# Transmission_Schematic.net
KiCad netlist of a schematic drawn in EAGLE
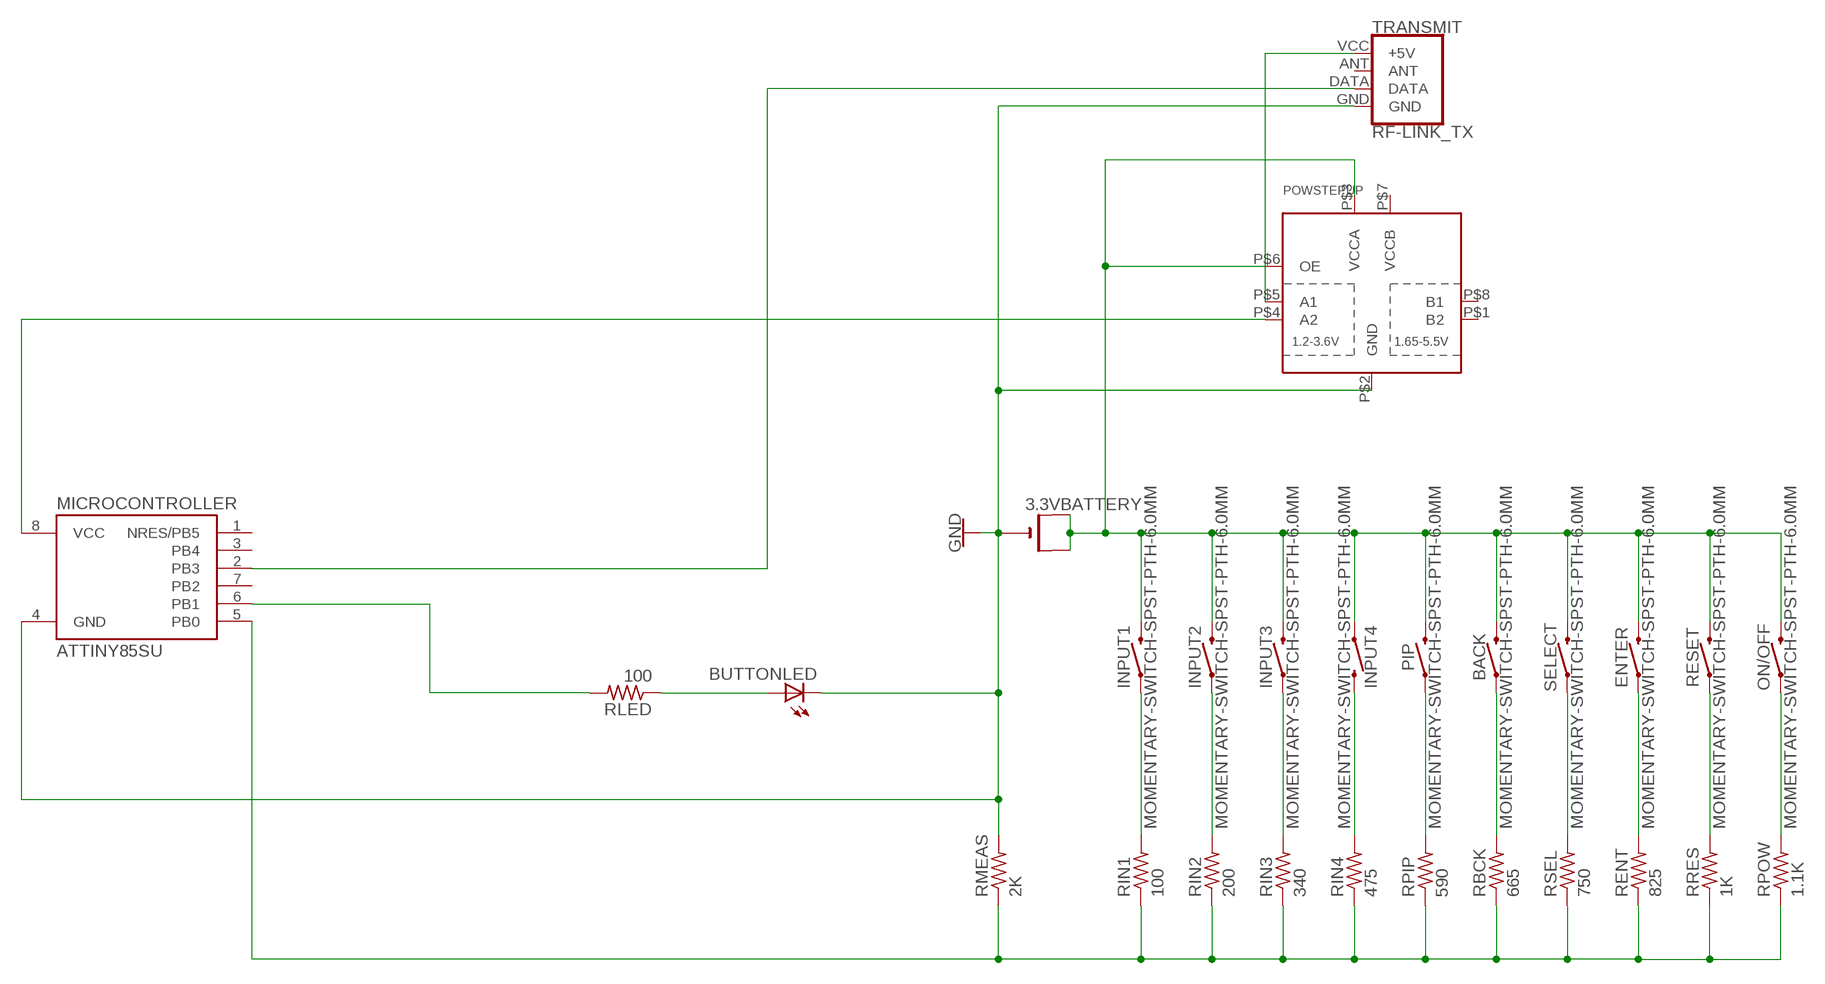
[diagram p0: schematic, sheet 1]

(export (version "E")
  (design (tool "Eeschema 10.0.6"))
  (components
    (comp (ref "3.3VBATTERY")
      (value "CR1220THM")
      (footprint "eagle-import:CR1220-THM")
      (libsource (lib "eagle-import") (part "CR1220THM"))
    )
    (comp (ref "BACK")
      (value "MOMENTARY-SWITCH-SPST-PTH-6.0MM")
      (footprint "eagle-import:TACTILE_SWITCH_PTH_6.0MM")
      (libsource (lib "eagle-import") (part "MOMENTARY-SWITCH-SPST-PTH-6.0MM"))
    )
    (comp (ref "BUTTONLED")
      (value "LEDCHIPLED_0805")
      (footprint "eagle-import:CHIPLED_0805")
      (libsource (lib "eagle-import") (part "LEDCHIPLED_0805"))
    )
    (comp (ref "ENTER")
      (value "MOMENTARY-SWITCH-SPST-PTH-6.0MM")
      (footprint "eagle-import:TACTILE_SWITCH_PTH_6.0MM")
      (libsource (lib "eagle-import") (part "MOMENTARY-SWITCH-SPST-PTH-6.0MM"))
    )
    (comp (ref "INPUT1")
      (value "MOMENTARY-SWITCH-SPST-PTH-6.0MM")
      (footprint "eagle-import:TACTILE_SWITCH_PTH_6.0MM")
      (libsource (lib "eagle-import") (part "MOMENTARY-SWITCH-SPST-PTH-6.0MM"))
    )
    (comp (ref "INPUT2")
      (value "MOMENTARY-SWITCH-SPST-PTH-6.0MM")
      (footprint "eagle-import:TACTILE_SWITCH_PTH_6.0MM")
      (libsource (lib "eagle-import") (part "MOMENTARY-SWITCH-SPST-PTH-6.0MM"))
    )
    (comp (ref "INPUT3")
      (value "MOMENTARY-SWITCH-SPST-PTH-6.0MM")
      (footprint "eagle-import:TACTILE_SWITCH_PTH_6.0MM")
      (libsource (lib "eagle-import") (part "MOMENTARY-SWITCH-SPST-PTH-6.0MM"))
    )
    (comp (ref "INPUT4")
      (value "MOMENTARY-SWITCH-SPST-PTH-6.0MM")
      (footprint "eagle-import:TACTILE_SWITCH_PTH_6.0MM")
      (libsource (lib "eagle-import") (part "MOMENTARY-SWITCH-SPST-PTH-6.0MM"))
    )
    (comp (ref "MICROCONTROLLER")
      (value "ATTINY85SU")
      (footprint "eagle-import:ATTINY85")
      (libsource (lib "eagle-import") (part "ATTINY85SU"))
    )
    (comp (ref "ON/OFF")
      (value "MOMENTARY-SWITCH-SPST-PTH-6.0MM")
      (footprint "eagle-import:TACTILE_SWITCH_PTH_6.0MM")
      (libsource (lib "eagle-import") (part "MOMENTARY-SWITCH-SPST-PTH-6.0MM"))
    )
    (comp (ref "PIP")
      (value "MOMENTARY-SWITCH-SPST-PTH-6.0MM")
      (footprint "eagle-import:TACTILE_SWITCH_PTH_6.0MM")
      (libsource (lib "eagle-import") (part "MOMENTARY-SWITCH-SPST-PTH-6.0MM"))
    )
    (comp (ref "POWSTEPUP")
      (value "TXS0102")
      (footprint "eagle-import:VFSOP-8")
      (libsource (lib "eagle-import") (part "TXS0102"))
    )
    (comp (ref "RBCK")
      (value "665")
      (footprint "eagle-import:R0805")
      (libsource (lib "eagle-import") (part "R-US_R0805"))
    )
    (comp (ref "RENT")
      (value "825")
      (footprint "eagle-import:R0805")
      (libsource (lib "eagle-import") (part "R-US_R0805"))
    )
    (comp (ref "RESET")
      (value "MOMENTARY-SWITCH-SPST-PTH-6.0MM")
      (footprint "eagle-import:TACTILE_SWITCH_PTH_6.0MM")
      (libsource (lib "eagle-import") (part "MOMENTARY-SWITCH-SPST-PTH-6.0MM"))
    )
    (comp (ref "RIN1")
      (value "100")
      (footprint "eagle-import:R0805")
      (libsource (lib "eagle-import") (part "R-US_R0805"))
    )
    (comp (ref "RIN2")
      (value "200")
      (footprint "eagle-import:R0805")
      (libsource (lib "eagle-import") (part "R-US_R0805"))
    )
    (comp (ref "RIN3")
      (value "340")
      (footprint "eagle-import:R0805")
      (libsource (lib "eagle-import") (part "R-US_R0805"))
    )
    (comp (ref "RIN4")
      (value "475")
      (footprint "eagle-import:R0805")
      (libsource (lib "eagle-import") (part "R-US_R0805"))
    )
    (comp (ref "RLED")
      (value "100")
      (footprint "eagle-import:R0805")
      (libsource (lib "eagle-import") (part "R-US_R0805"))
    )
    (comp (ref "RMEAS")
      (value "2K")
      (footprint "eagle-import:R0805")
      (libsource (lib "eagle-import") (part "R-US_R0805"))
    )
    (comp (ref "RPIP")
      (value "590")
      (footprint "eagle-import:R0805")
      (libsource (lib "eagle-import") (part "R-US_R0805"))
    )
    (comp (ref "RPOW")
      (value "1.1K")
      (footprint "eagle-import:R0805")
      (libsource (lib "eagle-import") (part "R-US_R0805"))
    )
    (comp (ref "RRES")
      (value "1K")
      (footprint "eagle-import:R0805")
      (libsource (lib "eagle-import") (part "R-US_R0805"))
    )
    (comp (ref "RSEL")
      (value "750")
      (footprint "eagle-import:R0805")
      (libsource (lib "eagle-import") (part "R-US_R0805"))
    )
    (comp (ref "SELECT")
      (value "MOMENTARY-SWITCH-SPST-PTH-6.0MM")
      (footprint "eagle-import:TACTILE_SWITCH_PTH_6.0MM")
      (libsource (lib "eagle-import") (part "MOMENTARY-SWITCH-SPST-PTH-6.0MM"))
    )
    (comp (ref "TRANSMIT")
      (value "RF-LINK_TX")
      (footprint "eagle-import:RF-LINK_TX")
      (libsource (lib "eagle-import") (part "RF-LINK_TX"))
    )
  )
  (nets
    (net (code "1") (name "GND") (class "Default")
      (node (ref "3.3VBATTERY") (pin "-") (pinfunction "-_-") (pintype "passive"))
      (node (ref "BUTTONLED") (pin "C") (pinfunction "C_C") (pintype "passive"))
      (node (ref "MICROCONTROLLER") (pin "4") (pinfunction "GND_4") (pintype "power_in"))
      (node (ref "POWSTEPUP") (pin "P$2") (pinfunction "GND_P$2") (pintype "bidirectional"))
      (node (ref "RMEAS") (pin "2") (pinfunction "2_2") (pintype "passive"))
      (node (ref "TRANSMIT") (pin "GND") (pinfunction "GND_GND") (pintype "power_in"))
    )
    (net (code "2") (name "Net-(3.3VBATTERY-+)") (class "Default")
      (node (ref "3.3VBATTERY") (pin "+1") (pinfunction "+_+1") (pintype "passive"))
      (node (ref "3.3VBATTERY") (pin "+2") (pinfunction "+1_+2") (pintype "passive"))
      (node (ref "BACK") (pin "3") (pinfunction "2_3") (pintype "passive"))
      (node (ref "ENTER") (pin "3") (pinfunction "2_3") (pintype "passive"))
      (node (ref "INPUT1") (pin "3") (pinfunction "2_3") (pintype "passive"))
      (node (ref "INPUT2") (pin "3") (pinfunction "2_3") (pintype "passive"))
      (node (ref "INPUT3") (pin "3") (pinfunction "2_3") (pintype "passive"))
      (node (ref "INPUT4") (pin "1") (pinfunction "1_1") (pintype "passive"))
      (node (ref "ON/OFF") (pin "3") (pinfunction "2_3") (pintype "passive"))
      (node (ref "PIP") (pin "3") (pinfunction "2_3") (pintype "passive"))
      (node (ref "POWSTEPUP") (pin "P$3") (pinfunction "VCCA_P$3") (pintype "bidirectional"))
      (node (ref "POWSTEPUP") (pin "P$6") (pinfunction "OE_P$6") (pintype "bidirectional"))
      (node (ref "RESET") (pin "3") (pinfunction "2_3") (pintype "passive"))
      (node (ref "SELECT") (pin "3") (pinfunction "2_3") (pintype "passive"))
    )
    (net (code "3") (name "Net-(BACK-Pad1)") (class "Default")
      (node (ref "BACK") (pin "1") (pinfunction "1_1") (pintype "passive"))
      (node (ref "RBCK") (pin "2") (pinfunction "2_2") (pintype "passive"))
    )
    (net (code "4") (name "Net-(BUTTONLED-PadA)") (class "Default")
      (node (ref "BUTTONLED") (pin "A") (pinfunction "A_A") (pintype "passive"))
      (node (ref "RLED") (pin "1") (pinfunction "1_1") (pintype "passive"))
    )
    (net (code "5") (name "Net-(ENTER-Pad1)") (class "Default")
      (node (ref "ENTER") (pin "1") (pinfunction "1_1") (pintype "passive"))
      (node (ref "RENT") (pin "2") (pinfunction "2_2") (pintype "passive"))
    )
    (net (code "6") (name "Net-(INPUT1-Pad1)") (class "Default")
      (node (ref "INPUT1") (pin "1") (pinfunction "1_1") (pintype "passive"))
      (node (ref "RIN1") (pin "2") (pinfunction "2_2") (pintype "passive"))
    )
    (net (code "7") (name "Net-(INPUT2-Pad1)") (class "Default")
      (node (ref "INPUT2") (pin "1") (pinfunction "1_1") (pintype "passive"))
      (node (ref "RIN2") (pin "2") (pinfunction "2_2") (pintype "passive"))
    )
    (net (code "8") (name "Net-(INPUT3-Pad1)") (class "Default")
      (node (ref "INPUT3") (pin "1") (pinfunction "1_1") (pintype "passive"))
      (node (ref "RIN3") (pin "2") (pinfunction "2_2") (pintype "passive"))
    )
    (net (code "9") (name "Net-(INPUT4-2)") (class "Default")
      (node (ref "INPUT4") (pin "3") (pinfunction "2_3") (pintype "passive"))
      (node (ref "RIN4") (pin "2") (pinfunction "2_2") (pintype "passive"))
    )
    (net (code "10") (name "Net-(MICROCONTROLLER-PB0)") (class "Default")
      (node (ref "MICROCONTROLLER") (pin "5") (pinfunction "PB0_5") (pintype "bidirectional"))
      (node (ref "RBCK") (pin "1") (pinfunction "1_1") (pintype "passive"))
      (node (ref "RENT") (pin "1") (pinfunction "1_1") (pintype "passive"))
      (node (ref "RIN1") (pin "1") (pinfunction "1_1") (pintype "passive"))
      (node (ref "RIN2") (pin "1") (pinfunction "1_1") (pintype "passive"))
      (node (ref "RIN3") (pin "1") (pinfunction "1_1") (pintype "passive"))
      (node (ref "RIN4") (pin "1") (pinfunction "1_1") (pintype "passive"))
      (node (ref "RMEAS") (pin "1") (pinfunction "1_1") (pintype "passive"))
      (node (ref "RPIP") (pin "1") (pinfunction "1_1") (pintype "passive"))
      (node (ref "RPOW") (pin "1") (pinfunction "1_1") (pintype "passive"))
      (node (ref "RRES") (pin "1") (pinfunction "1_1") (pintype "passive"))
      (node (ref "RSEL") (pin "1") (pinfunction "1_1") (pintype "passive"))
    )
    (net (code "11") (name "Net-(MICROCONTROLLER-PB1)") (class "Default")
      (node (ref "MICROCONTROLLER") (pin "6") (pinfunction "PB1_6") (pintype "bidirectional"))
      (node (ref "RLED") (pin "2") (pinfunction "2_2") (pintype "passive"))
    )
    (net (code "12") (name "Net-(MICROCONTROLLER-PB3)") (class "Default")
      (node (ref "MICROCONTROLLER") (pin "2") (pinfunction "PB3_2") (pintype "bidirectional"))
      (node (ref "TRANSMIT") (pin "DATA") (pinfunction "DATA_DATA") (pintype "input"))
    )
    (net (code "13") (name "Net-(MICROCONTROLLER-VCC)") (class "Default")
      (node (ref "MICROCONTROLLER") (pin "8") (pinfunction "VCC_8") (pintype "power_in"))
      (node (ref "POWSTEPUP") (pin "P$4") (pinfunction "A2_P$4") (pintype "bidirectional"))
    )
    (net (code "14") (name "Net-(ON/OFF-Pad1)") (class "Default")
      (node (ref "ON/OFF") (pin "1") (pinfunction "1_1") (pintype "passive"))
      (node (ref "RPOW") (pin "2") (pinfunction "2_2") (pintype "passive"))
    )
    (net (code "15") (name "Net-(PIP-Pad1)") (class "Default")
      (node (ref "PIP") (pin "1") (pinfunction "1_1") (pintype "passive"))
      (node (ref "RPIP") (pin "2") (pinfunction "2_2") (pintype "passive"))
    )
    (net (code "16") (name "Net-(POWSTEPUP-A1)") (class "Default")
      (node (ref "POWSTEPUP") (pin "P$5") (pinfunction "A1_P$5") (pintype "bidirectional"))
      (node (ref "TRANSMIT") (pin "VCC") (pinfunction "+5V_VCC") (pintype "power_in"))
    )
    (net (code "17") (name "Net-(RESET-Pad1)") (class "Default")
      (node (ref "RESET") (pin "1") (pinfunction "1_1") (pintype "passive"))
      (node (ref "RRES") (pin "2") (pinfunction "2_2") (pintype "passive"))
    )
    (net (code "18") (name "Net-(RSEL-Pad2)") (class "Default")
      (node (ref "RSEL") (pin "2") (pinfunction "2_2") (pintype "passive"))
      (node (ref "SELECT") (pin "1") (pinfunction "1_1") (pintype "passive"))
    )
    (net (code "19") (name "unconnected-(MICROCONTROLLER-NRES{slash}PB5-Pad1)") (class "Default")
      (node (ref "MICROCONTROLLER") (pin "1") (pinfunction "NRES/PB5_1") (pintype "bidirectional"))
    )
    (net (code "20") (name "unconnected-(MICROCONTROLLER-PB2-Pad7)") (class "Default")
      (node (ref "MICROCONTROLLER") (pin "7") (pinfunction "PB2_7") (pintype "bidirectional"))
    )
    (net (code "21") (name "unconnected-(MICROCONTROLLER-PB4-Pad3)") (class "Default")
      (node (ref "MICROCONTROLLER") (pin "3") (pinfunction "PB4_3") (pintype "bidirectional"))
    )
    (net (code "22") (name "unconnected-(POWSTEPUP-B1-PadP$8)") (class "Default")
      (node (ref "POWSTEPUP") (pin "P$8") (pinfunction "B1_P$8") (pintype "bidirectional"))
    )
    (net (code "23") (name "unconnected-(POWSTEPUP-B2-PadP$1)") (class "Default")
      (node (ref "POWSTEPUP") (pin "P$1") (pinfunction "B2_P$1") (pintype "bidirectional"))
    )
    (net (code "24") (name "unconnected-(POWSTEPUP-VCCB-PadP$7)") (class "Default")
      (node (ref "POWSTEPUP") (pin "P$7") (pinfunction "VCCB_P$7") (pintype "bidirectional"))
    )
    (net (code "25") (name "unconnected-(TRANSMIT-PadANT)") (class "Default")
      (node (ref "TRANSMIT") (pin "ANT") (pinfunction "ANT_ANT") (pintype "passive"))
    )
  )
)
